# Main_BoardSchDoc.net
KiCad netlist of a schematic drawn in Altium Designer
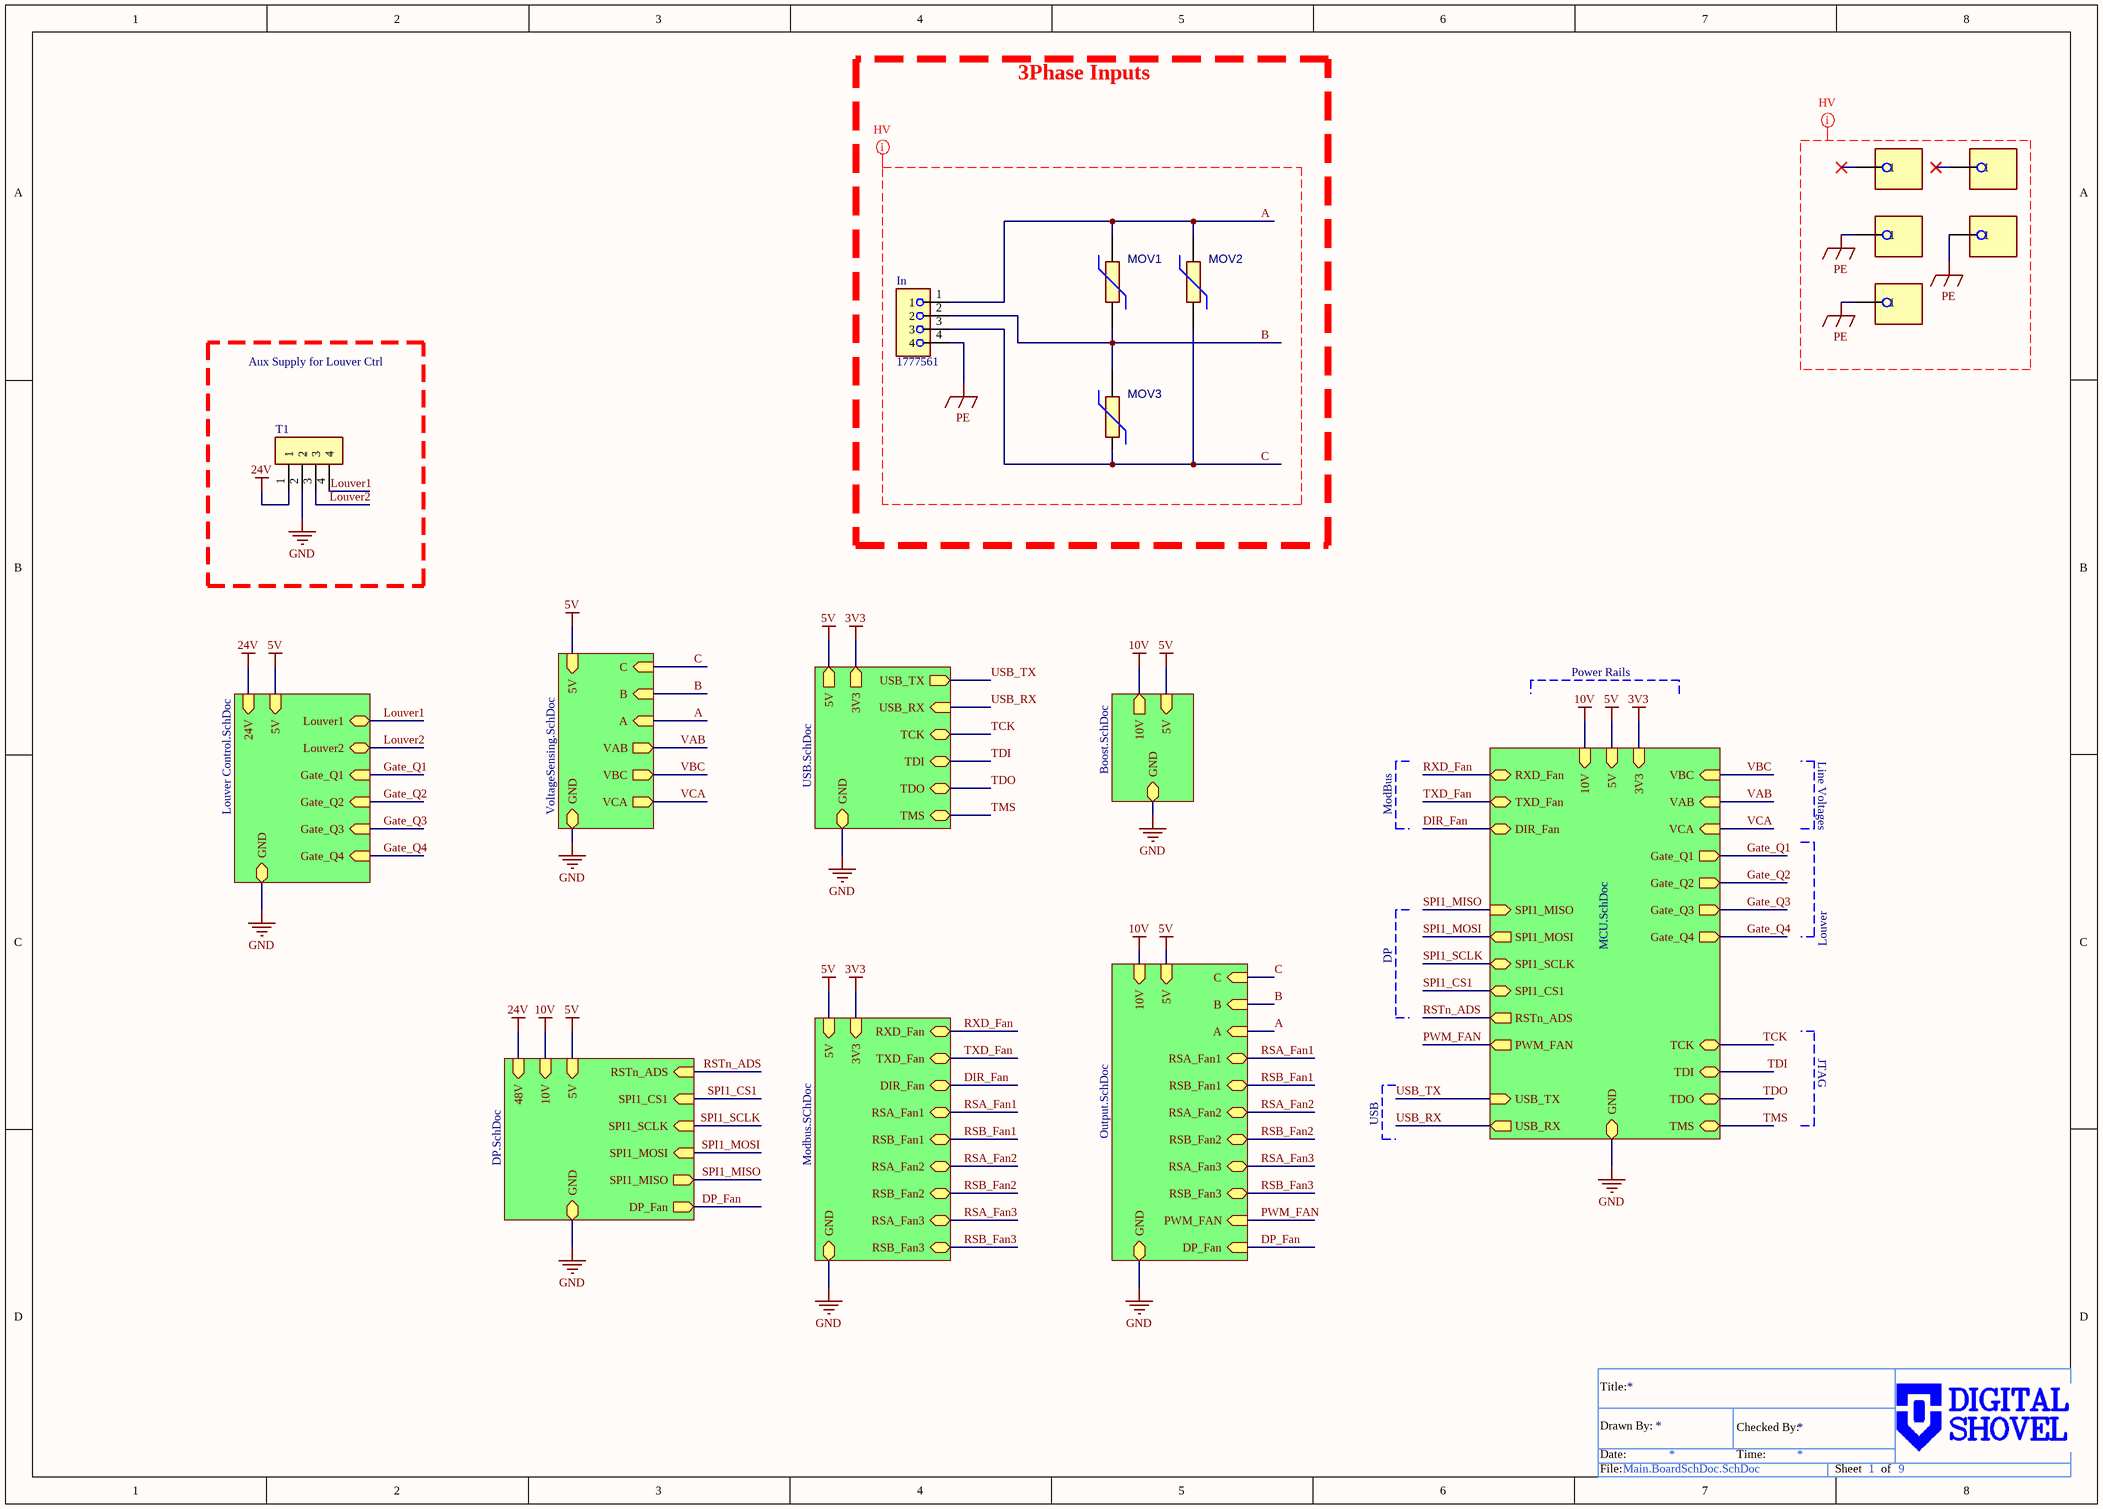
[diagram p0: Main.BoardSchDoc.SchDoc]

(export (version "E")
  (design (tool "Eeschema 10.0.6"))
  (components
    (comp (ref "1")
      (value "Mounting Hole")
      (footprint "Mounting Hole")
      (description "Aluminum 1/4 Hex Female Standoff, 4MM")
      (libsource (lib "Digital Shovel") (part "MH*"))
    )
    (comp (ref "3")
      (value "Mounting Hole")
      (footprint "Mounting Hole")
      (description "Aluminum 1/4 Hex Female Standoff, 4MM")
      (libsource (lib "Digital Shovel") (part "MH*"))
    )
    (comp (ref "4")
      (value "Mounting Hole")
      (footprint "Mounting Hole")
      (description "Aluminum 1/4 Hex Female Standoff, 4MM")
      (libsource (lib "Digital Shovel") (part "MH*"))
    )
    (comp (ref "5")
      (value "Mounting Hole")
      (footprint "Mounting Hole")
      (description "Aluminum 1/4 Hex Female Standoff, 4MM")
      (libsource (lib "Digital Shovel") (part "MH*"))
    )
    (comp (ref "6")
      (value "Mounting Hole")
      (footprint "Mounting Hole")
      (description "Aluminum 1/4 Hex Female Standoff, 4MM")
      (libsource (lib "Digital Shovel") (part "MH*"))
    )
    (comp (ref "In")
      (value "1777561")
      (footprint "1777561-Footprint-1")
      (description "4 Position Wire to Board Terminal Block Horizontal with Board 0.250\" (6.35mm) Through Hole")
      (libsource (lib "Digital Shovel") (part "1777561-Symbol-1"))
    )
    (comp (ref "MOV1")
      (value "MOV-14D102K")
      (footprint "MOV-14D102K-Footprint-1")
      (description "Varistor, 825V, 190J, Through Hole Mount")
      (fields (field (name "POWER") "600mW"))
      (libsource (lib "Digital Shovel") (part "RN73R2ATTD2003B25"))
    )
    (comp (ref "MOV2")
      (value "MOV-14D102K")
      (footprint "MOV-14D102K-Footprint-1")
      (description "Varistor, 825V, 190J, Through Hole Mount")
      (fields (field (name "POWER") "600mW"))
      (libsource (lib "Digital Shovel") (part "RN73R2ATTD2003B25"))
    )
    (comp (ref "MOV3")
      (value "MOV-14D102K")
      (footprint "MOV-14D102K-Footprint-1")
      (description "Varistor, 825V, 190J, Through Hole Mount")
      (fields (field (name "POWER") "600mW"))
      (libsource (lib "Digital Shovel") (part "RN73R2ATTD2003B25"))
    )
    (comp (ref "T1")
      (value "1984633")
      (footprint "1984633-Footprint-1")
      (description "Barrier Strip Terminal Block, 17.5A, 1.5mm2, 1 Row(s), 1 Deck(s)")
      (libsource (lib "Digital Shovel") (part "1984633-Symbol-1"))
    )
  )
  (nets
    (net (code "1") (name "/A") (class "Default")
      (node (ref "In") (pin "1") (pinfunction "1_1") (pintype "passive"))
      (node (ref "MOV1") (pin "2") (pinfunction "2_2") (pintype "passive"))
      (node (ref "MOV2") (pin "2") (pinfunction "2_2") (pintype "passive"))
    )
    (net (code "2") (name "/B") (class "Default")
      (node (ref "In") (pin "2") (pinfunction "2_2") (pintype "passive"))
      (node (ref "MOV1") (pin "1") (pinfunction "1_1") (pintype "passive"))
      (node (ref "MOV3") (pin "2") (pinfunction "2_2") (pintype "passive"))
    )
    (net (code "3") (name "/C") (class "Default")
      (node (ref "In") (pin "3") (pinfunction "3_3") (pintype "passive"))
      (node (ref "MOV2") (pin "1") (pinfunction "1_1") (pintype "passive"))
      (node (ref "MOV3") (pin "1") (pinfunction "1_1") (pintype "passive"))
    )
    (net (code "10") (name "/Louver1") (class "Default")
      (node (ref "T1") (pin "4") (pinfunction "4_4") (pintype "passive"))
    )
    (net (code "11") (name "/Louver2") (class "Default")
      (node (ref "T1") (pin "3") (pinfunction "3_3") (pintype "passive"))
    )
    (net (code "38") (name "24V") (class "Default")
      (node (ref "T1") (pin "1") (pinfunction "1_1") (pintype "passive"))
    )
    (net (code "39") (name "GND") (class "Default")
      (node (ref "T1") (pin "2") (pinfunction "2_2") (pintype "passive"))
    )
    (net (code "40") (name "PE") (class "Default")
      (node (ref "1") (pin "1") (pinfunction "1_1") (pintype "passive"))
      (node (ref "5") (pin "1") (pinfunction "1_1") (pintype "passive"))
      (node (ref "6") (pin "1") (pinfunction "1_1") (pintype "passive"))
      (node (ref "In") (pin "4") (pinfunction "4_4") (pintype "passive"))
    )
    (net (code "41") (name "unconnected-(3-Pad1)") (class "Default")
      (node (ref "3") (pin "1") (pinfunction "1_1") (pintype "passive+no_connect"))
    )
    (net (code "42") (name "unconnected-(4-Pad1)") (class "Default")
      (node (ref "4") (pin "1") (pinfunction "1_1") (pintype "passive+no_connect"))
    )
  )
)
